# Callisto_RSO_PB_Relay_x_4.net
KiCad netlist of a schematic drawn in EAGLE
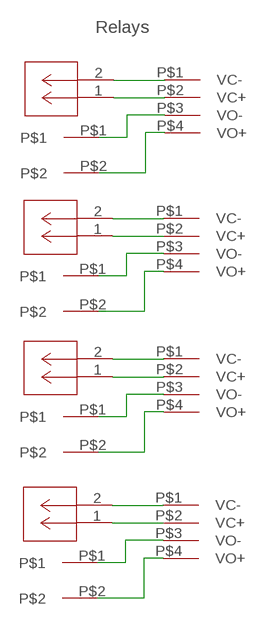
[diagram p0: schematic, sheet 1]

(export (version "E")
  (design (tool "Eeschema 10.0.6"))
  (components
    (comp (ref "J4")
      (value "CONN_530470210_PICOBLADE_X_2")
      (footprint "eagle-import:CON_530470210_MOL")
      (fields
        (field (name "MANUFACTURER_PART_NUMBER") "530470210")
        (field (name "COPYRIGHT") "Copyright (C) 2022 Ultra Librarian. All rights reserved.")
      )
      (libsource (lib "eagle-import") (part "CONN_530470210_PICOBLADE_X_2"))
    )
    (comp (ref "J5")
      (value "2-pos")
      (footprint "eagle-import:2_3.81MM_PITCH")
      (fields (field (name "PARTNO") "691322310002"))
      (libsource (lib "eagle-import") (part "3.81MM_1_X_2_RT_ANGLE_PLUG_HEADER"))
    )
    (comp (ref "J6")
      (value "CONN_530470210_PICOBLADE_X_2")
      (footprint "eagle-import:CON_530470210_MOL")
      (fields
        (field (name "MANUFACTURER_PART_NUMBER") "530470210")
        (field (name "COPYRIGHT") "Copyright (C) 2022 Ultra Librarian. All rights reserved.")
      )
      (libsource (lib "eagle-import") (part "CONN_530470210_PICOBLADE_X_2"))
    )
    (comp (ref "J7")
      (value "2-pos")
      (footprint "eagle-import:2_3.81MM_PITCH")
      (fields (field (name "PARTNO") "691322310002"))
      (libsource (lib "eagle-import") (part "3.81MM_1_X_2_RT_ANGLE_PLUG_HEADER"))
    )
    (comp (ref "J8")
      (value "CONN_530470210_PICOBLADE_X_2")
      (footprint "eagle-import:CON_530470210_MOL")
      (fields
        (field (name "MANUFACTURER_PART_NUMBER") "530470210")
        (field (name "COPYRIGHT") "Copyright (C) 2022 Ultra Librarian. All rights reserved.")
      )
      (libsource (lib "eagle-import") (part "CONN_530470210_PICOBLADE_X_2"))
    )
    (comp (ref "J9")
      (value "2-pos")
      (footprint "eagle-import:2_3.81MM_PITCH")
      (fields (field (name "PARTNO") "691322310002"))
      (libsource (lib "eagle-import") (part "3.81MM_1_X_2_RT_ANGLE_PLUG_HEADER"))
    )
    (comp (ref "J10")
      (value "CONN_530470210_PICOBLADE_X_2")
      (footprint "eagle-import:CON_530470210_MOL")
      (fields
        (field (name "MANUFACTURER_PART_NUMBER") "530470210")
        (field (name "COPYRIGHT") "Copyright (C) 2022 Ultra Librarian. All rights reserved.")
      )
      (libsource (lib "eagle-import") (part "CONN_530470210_PICOBLADE_X_2"))
    )
    (comp (ref "J11")
      (value "2-pos")
      (footprint "eagle-import:2_3.81MM_PITCH")
      (fields (field (name "PARTNO") "691322310002"))
      (libsource (lib "eagle-import") (part "3.81MM_1_X_2_RT_ANGLE_PLUG_HEADER"))
    )
    (comp (ref "U$1")
      (value "RELAY_KYOTO_KF0604D")
      (footprint "eagle-import:RELAY_KYOTO_KF0604D")
      (libsource (lib "eagle-import") (part "RELAY_KYOTO_KF0604D"))
    )
    (comp (ref "U$2")
      (value "RELAY_KYOTO_KF0604D")
      (footprint "eagle-import:RELAY_KYOTO_KF0604D")
      (libsource (lib "eagle-import") (part "RELAY_KYOTO_KF0604D"))
    )
    (comp (ref "U$3")
      (value "RELAY_KYOTO_KF0604D")
      (footprint "eagle-import:RELAY_KYOTO_KF0604D")
      (libsource (lib "eagle-import") (part "RELAY_KYOTO_KF0604D"))
    )
    (comp (ref "U$4")
      (value "RELAY_KYOTO_KF0604D")
      (footprint "eagle-import:RELAY_KYOTO_KF0604D")
      (libsource (lib "eagle-import") (part "RELAY_KYOTO_KF0604D"))
    )
  )
  (nets
    (net (code "1") (name "Net-(U$1-VC+)") (class "Default")
      (node (ref "J4") (pin "1") (pinfunction "1_1") (pintype "passive"))
      (node (ref "U$1") (pin "P$2") (pinfunction "VC+_P$2") (pintype "bidirectional"))
    )
    (net (code "2") (name "Net-(U$1-VC-)") (class "Default")
      (node (ref "J4") (pin "2") (pinfunction "2_2") (pintype "passive"))
      (node (ref "U$1") (pin "P$1") (pinfunction "VC-_P$1") (pintype "bidirectional"))
    )
    (net (code "3") (name "Net-(U$1-VO+)") (class "Default")
      (node (ref "J5") (pin "P$2") (pinfunction "P$2_P$2") (pintype "bidirectional"))
      (node (ref "U$1") (pin "P$4") (pinfunction "VO+_P$4") (pintype "bidirectional"))
    )
    (net (code "4") (name "Net-(U$1-VO-)") (class "Default")
      (node (ref "J5") (pin "P$1") (pinfunction "P$1_P$1") (pintype "bidirectional"))
      (node (ref "U$1") (pin "P$3") (pinfunction "VO-_P$3") (pintype "bidirectional"))
    )
    (net (code "5") (name "Net-(U$2-VC+)") (class "Default")
      (node (ref "J6") (pin "1") (pinfunction "1_1") (pintype "passive"))
      (node (ref "U$2") (pin "P$2") (pinfunction "VC+_P$2") (pintype "bidirectional"))
    )
    (net (code "6") (name "Net-(U$2-VC-)") (class "Default")
      (node (ref "J6") (pin "2") (pinfunction "2_2") (pintype "passive"))
      (node (ref "U$2") (pin "P$1") (pinfunction "VC-_P$1") (pintype "bidirectional"))
    )
    (net (code "7") (name "Net-(U$2-VO+)") (class "Default")
      (node (ref "J7") (pin "P$2") (pinfunction "P$2_P$2") (pintype "bidirectional"))
      (node (ref "U$2") (pin "P$4") (pinfunction "VO+_P$4") (pintype "bidirectional"))
    )
    (net (code "8") (name "Net-(U$2-VO-)") (class "Default")
      (node (ref "J7") (pin "P$1") (pinfunction "P$1_P$1") (pintype "bidirectional"))
      (node (ref "U$2") (pin "P$3") (pinfunction "VO-_P$3") (pintype "bidirectional"))
    )
    (net (code "9") (name "Net-(U$3-VC+)") (class "Default")
      (node (ref "J8") (pin "1") (pinfunction "1_1") (pintype "passive"))
      (node (ref "U$3") (pin "P$2") (pinfunction "VC+_P$2") (pintype "bidirectional"))
    )
    (net (code "10") (name "Net-(U$3-VC-)") (class "Default")
      (node (ref "J8") (pin "2") (pinfunction "2_2") (pintype "passive"))
      (node (ref "U$3") (pin "P$1") (pinfunction "VC-_P$1") (pintype "bidirectional"))
    )
    (net (code "11") (name "Net-(U$3-VO+)") (class "Default")
      (node (ref "J9") (pin "P$2") (pinfunction "P$2_P$2") (pintype "bidirectional"))
      (node (ref "U$3") (pin "P$4") (pinfunction "VO+_P$4") (pintype "bidirectional"))
    )
    (net (code "12") (name "Net-(U$3-VO-)") (class "Default")
      (node (ref "J9") (pin "P$1") (pinfunction "P$1_P$1") (pintype "bidirectional"))
      (node (ref "U$3") (pin "P$3") (pinfunction "VO-_P$3") (pintype "bidirectional"))
    )
    (net (code "13") (name "Net-(U$4-VC+)") (class "Default")
      (node (ref "J10") (pin "1") (pinfunction "1_1") (pintype "passive"))
      (node (ref "U$4") (pin "P$2") (pinfunction "VC+_P$2") (pintype "bidirectional"))
    )
    (net (code "14") (name "Net-(U$4-VC-)") (class "Default")
      (node (ref "J10") (pin "2") (pinfunction "2_2") (pintype "passive"))
      (node (ref "U$4") (pin "P$1") (pinfunction "VC-_P$1") (pintype "bidirectional"))
    )
    (net (code "15") (name "Net-(U$4-VO+)") (class "Default")
      (node (ref "J11") (pin "P$2") (pinfunction "P$2_P$2") (pintype "bidirectional"))
      (node (ref "U$4") (pin "P$4") (pinfunction "VO+_P$4") (pintype "bidirectional"))
    )
    (net (code "16") (name "Net-(U$4-VO-)") (class "Default")
      (node (ref "J11") (pin "P$1") (pinfunction "P$1_P$1") (pintype "bidirectional"))
      (node (ref "U$4") (pin "P$3") (pinfunction "VO-_P$3") (pintype "bidirectional"))
    )
  )
)
